# charger_4012.net
KiCad netlist of a schematic drawn in EAGLE
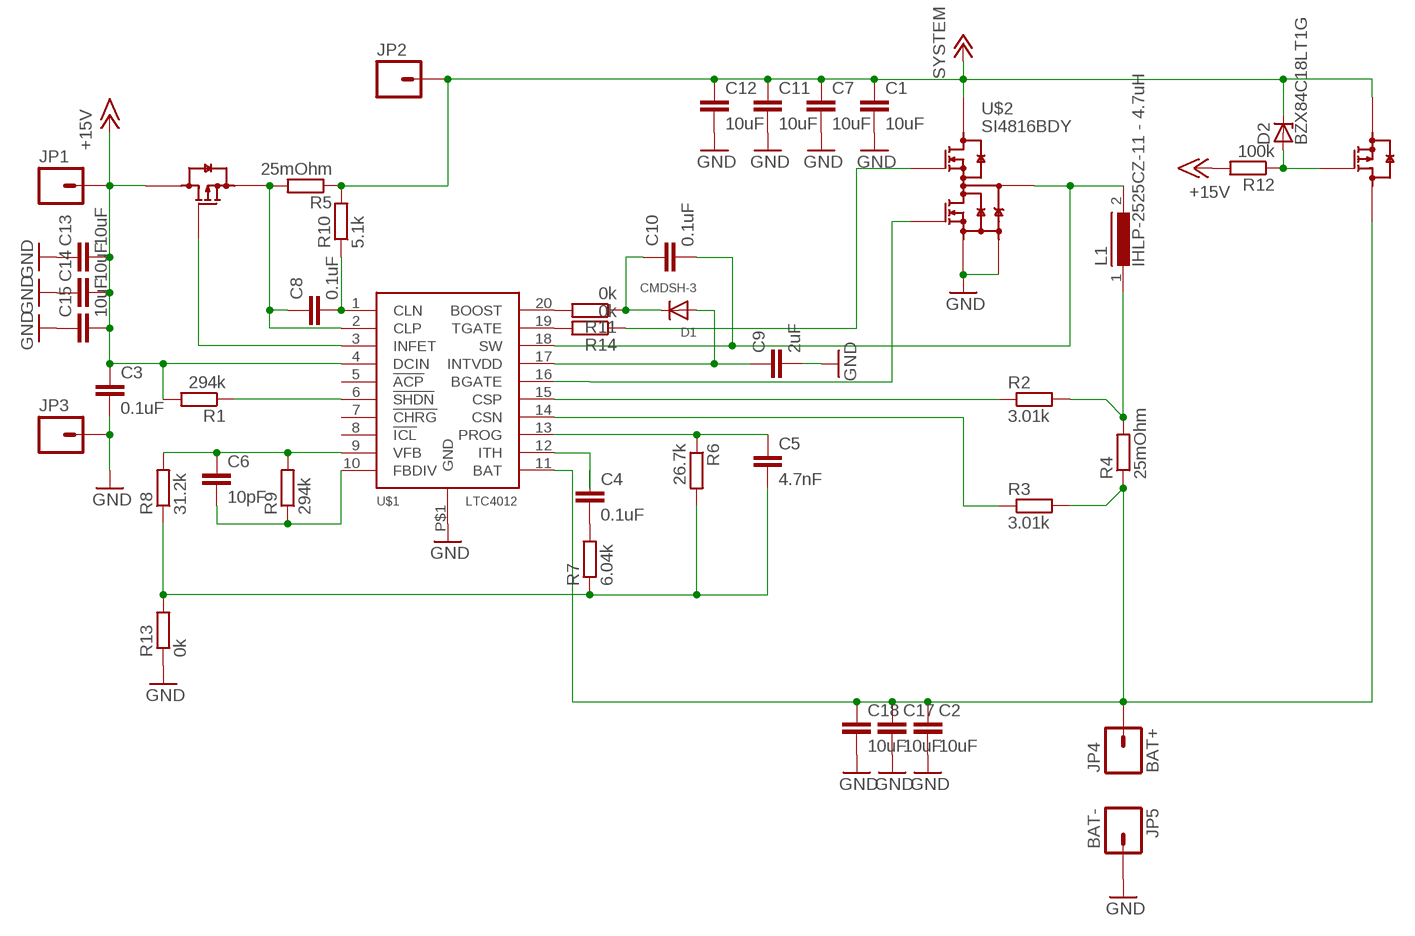
[diagram p0: schematic, sheet 1]

(export (version "E")
  (design (tool "Eeschema 10.0.6"))
  (components
    (comp (ref "C1")
      (value "10uF")
      (footprint "eagle-import:C1206")
      (libsource (lib "eagle-import") (part "C-EUC1206"))
    )
    (comp (ref "C2")
      (value "10uF")
      (footprint "eagle-import:C1206")
      (libsource (lib "eagle-import") (part "C-EUC1206"))
    )
    (comp (ref "C3")
      (value "0.1uF")
      (footprint "eagle-import:C0402")
      (libsource (lib "eagle-import") (part "C-EUC0402"))
    )
    (comp (ref "C4")
      (value "0.1uF")
      (footprint "eagle-import:C0402")
      (libsource (lib "eagle-import") (part "C-EUC0402"))
    )
    (comp (ref "C5")
      (value "4.7nF")
      (footprint "eagle-import:C0402")
      (libsource (lib "eagle-import") (part "C-EUC0402"))
    )
    (comp (ref "C6")
      (value "10pF")
      (footprint "eagle-import:C0402")
      (libsource (lib "eagle-import") (part "C-EUC0402"))
    )
    (comp (ref "C7")
      (value "10uF")
      (footprint "eagle-import:C1206")
      (libsource (lib "eagle-import") (part "C-EUC1206"))
    )
    (comp (ref "C8")
      (value "0.1uF")
      (footprint "eagle-import:C0402")
      (libsource (lib "eagle-import") (part "C-EUC0402"))
    )
    (comp (ref "C9")
      (value "2uF")
      (footprint "eagle-import:C0805")
      (libsource (lib "eagle-import") (part "C-EUC0805"))
    )
    (comp (ref "C10")
      (value "0.1uF")
      (footprint "eagle-import:C0402")
      (libsource (lib "eagle-import") (part "C-EUC0402"))
    )
    (comp (ref "C11")
      (value "10uF")
      (footprint "eagle-import:C1206")
      (libsource (lib "eagle-import") (part "C-EUC1206"))
    )
    (comp (ref "C12")
      (value "10uF")
      (footprint "eagle-import:C1206")
      (libsource (lib "eagle-import") (part "C-EUC1206"))
    )
    (comp (ref "C13")
      (value "10uF")
      (footprint "eagle-import:C1206")
      (libsource (lib "eagle-import") (part "C-EUC1206"))
    )
    (comp (ref "C14")
      (value "10uF")
      (footprint "eagle-import:C1206")
      (libsource (lib "eagle-import") (part "C-EUC1206"))
    )
    (comp (ref "C15")
      (value "10uF")
      (footprint "eagle-import:C1206")
      (libsource (lib "eagle-import") (part "C-EUC1206"))
    )
    (comp (ref "C17")
      (value "10uF")
      (footprint "eagle-import:C1206")
      (libsource (lib "eagle-import") (part "C-EUC1206"))
    )
    (comp (ref "C18")
      (value "10uF")
      (footprint "eagle-import:C1206")
      (libsource (lib "eagle-import") (part "C-EUC1206"))
    )
    (comp (ref "D1")
      (value "CMDSH-3")
      (footprint "eagle-import:SOD-323F")
      (libsource (lib "eagle-import") (part "DIODESOD-323F"))
    )
    (comp (ref "D2")
      (value "BZX84C18LT1G")
      (footprint "eagle-import:TO236")
      (libsource (lib "eagle-import") (part "ZENER-DIODETO236"))
    )
    (comp (ref "JP1")
      (value "M01PTH_2MM")
      (footprint "eagle-import:1X01_2MM")
      (libsource (lib "eagle-import") (part "M01PTH_2MM"))
    )
    (comp (ref "JP2")
      (value "M01PTH_2MM")
      (footprint "eagle-import:1X01_2MM")
      (libsource (lib "eagle-import") (part "M01PTH_2MM"))
    )
    (comp (ref "JP3")
      (value "M01PTH_2MM")
      (footprint "eagle-import:1X01_2MM")
      (libsource (lib "eagle-import") (part "M01PTH_2MM"))
    )
    (comp (ref "JP4")
      (value "BAT+")
      (footprint "eagle-import:1X01_2MM")
      (libsource (lib "eagle-import") (part "M01PTH_2MM"))
    )
    (comp (ref "JP5")
      (value "BAT-")
      (footprint "eagle-import:1X01_2MM")
      (libsource (lib "eagle-import") (part "M01PTH_2MM"))
    )
    (comp (ref "L1")
      (value "IHLP-2525CZ-11 - 4.7uH")
      (footprint "eagle-import:DR73")
      (libsource (lib "eagle-import") (part "DR73"))
    )
    (comp (ref "R1")
      (value "294k")
      (footprint "eagle-import:R0402")
      (libsource (lib "eagle-import") (part "R-EU_R0402"))
    )
    (comp (ref "R2")
      (value "3.01k")
      (footprint "eagle-import:R0402")
      (libsource (lib "eagle-import") (part "R-EU_R0402"))
    )
    (comp (ref "R3")
      (value "3.01k")
      (footprint "eagle-import:R0402")
      (libsource (lib "eagle-import") (part "R-EU_R0402"))
    )
    (comp (ref "R4")
      (value "25mOhm")
      (footprint "eagle-import:R2512")
      (libsource (lib "eagle-import") (part "R-EU_R2512"))
    )
    (comp (ref "R5")
      (value "25mOhm")
      (footprint "eagle-import:R2512")
      (libsource (lib "eagle-import") (part "R-EU_R2512"))
    )
    (comp (ref "R6")
      (value "26.7k")
      (footprint "eagle-import:R0402")
      (libsource (lib "eagle-import") (part "R-EU_R0402"))
    )
    (comp (ref "R7")
      (value "6.04k")
      (footprint "eagle-import:R0402")
      (libsource (lib "eagle-import") (part "R-EU_R0402"))
    )
    (comp (ref "R8")
      (value "31.2k")
      (footprint "eagle-import:R0402")
      (libsource (lib "eagle-import") (part "R-EU_R0402"))
    )
    (comp (ref "R9")
      (value "294k")
      (footprint "eagle-import:R0402")
      (libsource (lib "eagle-import") (part "R-EU_R0402"))
    )
    (comp (ref "R10")
      (value "5.1k")
      (footprint "eagle-import:R0402")
      (libsource (lib "eagle-import") (part "R-EU_R0402"))
    )
    (comp (ref "R11")
      (value "0k")
      (footprint "eagle-import:R0402")
      (libsource (lib "eagle-import") (part "R-EU_R0402"))
    )
    (comp (ref "R12")
      (value "100k")
      (footprint "eagle-import:R0402")
      (libsource (lib "eagle-import") (part "R-EU_R0402"))
    )
    (comp (ref "R13")
      (value "0k")
      (footprint "eagle-import:R0402")
      (libsource (lib "eagle-import") (part "R-EU_R0402"))
    )
    (comp (ref "R14")
      (value "0k")
      (footprint "eagle-import:R0402")
      (libsource (lib "eagle-import") (part "R-EU_R0402"))
    )
    (comp (ref "U$1")
      (value "LTC4012")
      (footprint "eagle-import:QFN20")
      (libsource (lib "eagle-import") (part "LTC4012"))
    )
    (comp (ref "U$2")
      (value "SI4816BDY")
      (footprint "eagle-import:SO-8")
      (libsource (lib "eagle-import") (part "SI4816BDY"))
    )
    (comp (ref "U$3")
      (value "SI7423DN")
      (footprint "eagle-import:POWERPACK1212")
      (libsource (lib "eagle-import") (part "SI7423DN"))
    )
    (comp (ref "U$4")
      (value "SI7423DN")
      (footprint "eagle-import:POWERPACK1212")
      (libsource (lib "eagle-import") (part "SI7423DN"))
    )
  )
  (nets
    (net (code "1") (name "+15V") (class "Default")
      (node (ref "C13") (pin "2") (pinfunction "2_2") (pintype "passive"))
      (node (ref "C14") (pin "2") (pinfunction "2_2") (pintype "passive"))
      (node (ref "C15") (pin "2") (pinfunction "2_2") (pintype "passive"))
      (node (ref "C3") (pin "1") (pinfunction "1_1") (pintype "passive"))
      (node (ref "JP1") (pin "1") (pinfunction "1_1") (pintype "passive"))
      (node (ref "R1") (pin "2") (pinfunction "2_2") (pintype "passive"))
      (node (ref "R12") (pin "2") (pinfunction "2_2") (pintype "passive"))
      (node (ref "U$1") (pin "4") (pinfunction "DCIN_4") (pintype "bidirectional"))
      (node (ref "U$3") (pin "5") (pinfunction "D_5") (pintype "bidirectional"))
      (node (ref "U$3") (pin "6") (pinfunction "D_6") (pintype "bidirectional"))
      (node (ref "U$3") (pin "7") (pinfunction "D_7") (pintype "bidirectional"))
      (node (ref "U$3") (pin "8") (pinfunction "D_8") (pintype "bidirectional"))
      (node (ref "U$3") (pin "9") (pinfunction "D_9") (pintype "bidirectional"))
    )
    (net (code "2") (name "GND") (class "Default")
      (node (ref "C1") (pin "2") (pinfunction "2_2") (pintype "passive"))
      (node (ref "C11") (pin "2") (pinfunction "2_2") (pintype "passive"))
      (node (ref "C12") (pin "2") (pinfunction "2_2") (pintype "passive"))
      (node (ref "C13") (pin "1") (pinfunction "1_1") (pintype "passive"))
      (node (ref "C14") (pin "1") (pinfunction "1_1") (pintype "passive"))
      (node (ref "C15") (pin "1") (pinfunction "1_1") (pintype "passive"))
      (node (ref "C17") (pin "2") (pinfunction "2_2") (pintype "passive"))
      (node (ref "C18") (pin "2") (pinfunction "2_2") (pintype "passive"))
      (node (ref "C2") (pin "2") (pinfunction "2_2") (pintype "passive"))
      (node (ref "C3") (pin "2") (pinfunction "2_2") (pintype "passive"))
      (node (ref "C7") (pin "2") (pinfunction "2_2") (pintype "passive"))
      (node (ref "C9") (pin "2") (pinfunction "2_2") (pintype "passive"))
      (node (ref "JP3") (pin "1") (pinfunction "1_1") (pintype "passive"))
      (node (ref "JP5") (pin "1") (pinfunction "1_1") (pintype "passive"))
      (node (ref "R13") (pin "1") (pinfunction "1_1") (pintype "passive"))
      (node (ref "U$1") (pin "P$1") (pinfunction "GND_P$1") (pintype "bidirectional"))
      (node (ref "U$2") (pin "2") (pinfunction "A_2") (pintype "bidirectional"))
      (node (ref "U$2") (pin "3") (pinfunction "S2_3") (pintype "bidirectional"))
    )
    (net (code "3") (name "Net-(C4-Pad2)") (class "Default")
      (node (ref "C4") (pin "2") (pinfunction "2_2") (pintype "passive"))
      (node (ref "R7") (pin "2") (pinfunction "2_2") (pintype "passive"))
    )
    (net (code "4") (name "Net-(C5-Pad2)") (class "Default")
      (node (ref "C5") (pin "2") (pinfunction "2_2") (pintype "passive"))
      (node (ref "R13") (pin "2") (pinfunction "2_2") (pintype "passive"))
      (node (ref "R6") (pin "2") (pinfunction "2_2") (pintype "passive"))
      (node (ref "R7") (pin "1") (pinfunction "1_1") (pintype "passive"))
      (node (ref "R8") (pin "1") (pinfunction "1_1") (pintype "passive"))
    )
    (net (code "5") (name "Net-(C10-Pad1)") (class "Default")
      (node (ref "C10") (pin "1") (pinfunction "1_1") (pintype "passive"))
      (node (ref "D1") (pin "C") (pinfunction "C_C") (pintype "passive"))
      (node (ref "R11") (pin "1") (pinfunction "1_1") (pintype "passive"))
    )
    (net (code "6") (name "Net-(L1-Pad1)") (class "Default")
      (node (ref "L1") (pin "1") (pinfunction "1_1") (pintype "passive"))
      (node (ref "R2") (pin "2") (pinfunction "2_2") (pintype "passive"))
      (node (ref "R4") (pin "2") (pinfunction "2_2") (pintype "passive"))
    )
    (net (code "7") (name "Net-(U$1-BAT)") (class "Default")
      (node (ref "C17") (pin "1") (pinfunction "1_1") (pintype "passive"))
      (node (ref "C18") (pin "1") (pinfunction "1_1") (pintype "passive"))
      (node (ref "C2") (pin "1") (pinfunction "1_1") (pintype "passive"))
      (node (ref "JP4") (pin "1") (pinfunction "1_1") (pintype "passive"))
      (node (ref "R3") (pin "2") (pinfunction "2_2") (pintype "passive"))
      (node (ref "R4") (pin "1") (pinfunction "1_1") (pintype "passive"))
      (node (ref "U$1") (pin "11") (pinfunction "BAT_11") (pintype "bidirectional"))
      (node (ref "U$4") (pin "5") (pinfunction "D_5") (pintype "bidirectional"))
      (node (ref "U$4") (pin "6") (pinfunction "D_6") (pintype "bidirectional"))
      (node (ref "U$4") (pin "7") (pinfunction "D_7") (pintype "bidirectional"))
      (node (ref "U$4") (pin "8") (pinfunction "D_8") (pintype "bidirectional"))
      (node (ref "U$4") (pin "9") (pinfunction "D_9") (pintype "bidirectional"))
    )
    (net (code "8") (name "Net-(U$1-BGATE)") (class "Default")
      (node (ref "U$1") (pin "16") (pinfunction "BGATE_16") (pintype "bidirectional"))
      (node (ref "U$2") (pin "4") (pinfunction "G2_4") (pintype "bidirectional"))
    )
    (net (code "9") (name "Net-(U$1-BOOST)") (class "Default")
      (node (ref "R11") (pin "2") (pinfunction "2_2") (pintype "passive"))
      (node (ref "U$1") (pin "20") (pinfunction "BOOST_20") (pintype "bidirectional"))
    )
    (net (code "10") (name "Net-(U$1-CLN)") (class "Default")
      (node (ref "C8") (pin "2") (pinfunction "2_2") (pintype "passive"))
      (node (ref "R10") (pin "1") (pinfunction "1_1") (pintype "passive"))
      (node (ref "U$1") (pin "1") (pinfunction "CLN_1") (pintype "bidirectional"))
    )
    (net (code "11") (name "Net-(U$1-CLP)") (class "Default")
      (node (ref "C8") (pin "1") (pinfunction "1_1") (pintype "passive"))
      (node (ref "R5") (pin "2") (pinfunction "2_2") (pintype "passive"))
      (node (ref "U$1") (pin "2") (pinfunction "CLP_2") (pintype "bidirectional"))
      (node (ref "U$3") (pin "1") (pinfunction "S_1") (pintype "bidirectional"))
      (node (ref "U$3") (pin "2") (pinfunction "S_2") (pintype "bidirectional"))
      (node (ref "U$3") (pin "3") (pinfunction "S_3") (pintype "bidirectional"))
    )
    (net (code "12") (name "Net-(U$1-CSN)") (class "Default")
      (node (ref "R3") (pin "1") (pinfunction "1_1") (pintype "passive"))
      (node (ref "U$1") (pin "14") (pinfunction "CSN_14") (pintype "bidirectional"))
    )
    (net (code "13") (name "Net-(U$1-CSP)") (class "Default")
      (node (ref "R2") (pin "1") (pinfunction "1_1") (pintype "passive"))
      (node (ref "U$1") (pin "15") (pinfunction "CSP_15") (pintype "bidirectional"))
    )
    (net (code "14") (name "Net-(U$1-FBDIV)") (class "Default")
      (node (ref "C6") (pin "2") (pinfunction "2_2") (pintype "passive"))
      (node (ref "R9") (pin "1") (pinfunction "1_1") (pintype "passive"))
      (node (ref "U$1") (pin "10") (pinfunction "FBDIV_10") (pintype "bidirectional"))
    )
    (net (code "15") (name "Net-(U$1-INFET)") (class "Default")
      (node (ref "U$1") (pin "3") (pinfunction "INFET_3") (pintype "bidirectional"))
      (node (ref "U$3") (pin "4") (pinfunction "G_4") (pintype "bidirectional"))
    )
    (net (code "16") (name "Net-(U$1-INTVDD)") (class "Default")
      (node (ref "C9") (pin "1") (pinfunction "1_1") (pintype "passive"))
      (node (ref "D1") (pin "A") (pinfunction "A_A") (pintype "passive"))
      (node (ref "U$1") (pin "17") (pinfunction "INTVDD_17") (pintype "bidirectional"))
    )
    (net (code "17") (name "Net-(U$1-ITH)") (class "Default")
      (node (ref "C4") (pin "1") (pinfunction "1_1") (pintype "passive"))
      (node (ref "U$1") (pin "12") (pinfunction "ITH_12") (pintype "bidirectional"))
    )
    (net (code "18") (name "Net-(U$1-PROG)") (class "Default")
      (node (ref "C5") (pin "1") (pinfunction "1_1") (pintype "passive"))
      (node (ref "R6") (pin "1") (pinfunction "1_1") (pintype "passive"))
      (node (ref "U$1") (pin "13") (pinfunction "PROG_13") (pintype "bidirectional"))
    )
    (net (code "19") (name "Net-(U$1-SW)") (class "Default")
      (node (ref "C10") (pin "2") (pinfunction "2_2") (pintype "passive"))
      (node (ref "L1") (pin "2") (pinfunction "2_2") (pintype "passive"))
      (node (ref "U$1") (pin "18") (pinfunction "SW_18") (pintype "bidirectional"))
      (node (ref "U$2") (pin "5") (pinfunction "S1/D2_5") (pintype "bidirectional"))
      (node (ref "U$2") (pin "6") (pinfunction "S1/D2_6") (pintype "bidirectional"))
      (node (ref "U$2") (pin "7") (pinfunction "S1/D2_7") (pintype "bidirectional"))
    )
    (net (code "20") (name "Net-(U$1-TGATE)") (class "Default")
      (node (ref "R14") (pin "2") (pinfunction "2_2") (pintype "passive"))
      (node (ref "U$1") (pin "19") (pinfunction "TGATE_19") (pintype "bidirectional"))
    )
    (net (code "21") (name "Net-(U$1-VFB)") (class "Default")
      (node (ref "C6") (pin "1") (pinfunction "1_1") (pintype "passive"))
      (node (ref "R8") (pin "2") (pinfunction "2_2") (pintype "passive"))
      (node (ref "R9") (pin "2") (pinfunction "2_2") (pintype "passive"))
      (node (ref "U$1") (pin "9") (pinfunction "VFB_9") (pintype "bidirectional"))
    )
    (net (code "22") (name "Net-(U$1-~{SHDN})") (class "Default")
      (node (ref "R1") (pin "1") (pinfunction "1_1") (pintype "passive"))
      (node (ref "U$1") (pin "6") (pinfunction "~{SHDN}_6") (pintype "bidirectional"))
    )
    (net (code "23") (name "Net-(U$2-G1)") (class "Default")
      (node (ref "R14") (pin "1") (pinfunction "1_1") (pintype "passive"))
      (node (ref "U$2") (pin "1") (pinfunction "G1_1") (pintype "bidirectional"))
    )
    (net (code "24") (name "Net-(U$4-G)") (class "Default")
      (node (ref "D2") (pin "A") (pinfunction "A_A") (pintype "passive"))
      (node (ref "R12") (pin "1") (pinfunction "1_1") (pintype "passive"))
      (node (ref "U$4") (pin "4") (pinfunction "G_4") (pintype "bidirectional"))
    )
    (net (code "25") (name "SYSTEM") (class "Default")
      (node (ref "C1") (pin "1") (pinfunction "1_1") (pintype "passive"))
      (node (ref "C11") (pin "1") (pinfunction "1_1") (pintype "passive"))
      (node (ref "C12") (pin "1") (pinfunction "1_1") (pintype "passive"))
      (node (ref "C7") (pin "1") (pinfunction "1_1") (pintype "passive"))
      (node (ref "D2") (pin "C") (pinfunction "C_C") (pintype "passive"))
      (node (ref "JP2") (pin "1") (pinfunction "1_1") (pintype "passive"))
      (node (ref "R10") (pin "2") (pinfunction "2_2") (pintype "passive"))
      (node (ref "R5") (pin "1") (pinfunction "1_1") (pintype "passive"))
      (node (ref "U$2") (pin "8") (pinfunction "D1_8") (pintype "bidirectional"))
      (node (ref "U$4") (pin "1") (pinfunction "S_1") (pintype "bidirectional"))
      (node (ref "U$4") (pin "2") (pinfunction "S_2") (pintype "bidirectional"))
      (node (ref "U$4") (pin "3") (pinfunction "S_3") (pintype "bidirectional"))
    )
    (net (code "26") (name "unconnected-(U$1-~{ACP}-Pad5)") (class "Default")
      (node (ref "U$1") (pin "5") (pinfunction "~{ACP}_5") (pintype "bidirectional"))
    )
    (net (code "27") (name "unconnected-(U$1-~{CHRG}-Pad7)") (class "Default")
      (node (ref "U$1") (pin "7") (pinfunction "~{CHRG}_7") (pintype "bidirectional"))
    )
    (net (code "28") (name "unconnected-(U$1-~{ICL}-Pad8)") (class "Default")
      (node (ref "U$1") (pin "8") (pinfunction "~{ICL}_8") (pintype "bidirectional"))
    )
  )
)
